# Mtx12BR_v1_1.net
KiCad netlist of a schematic drawn in EAGLE
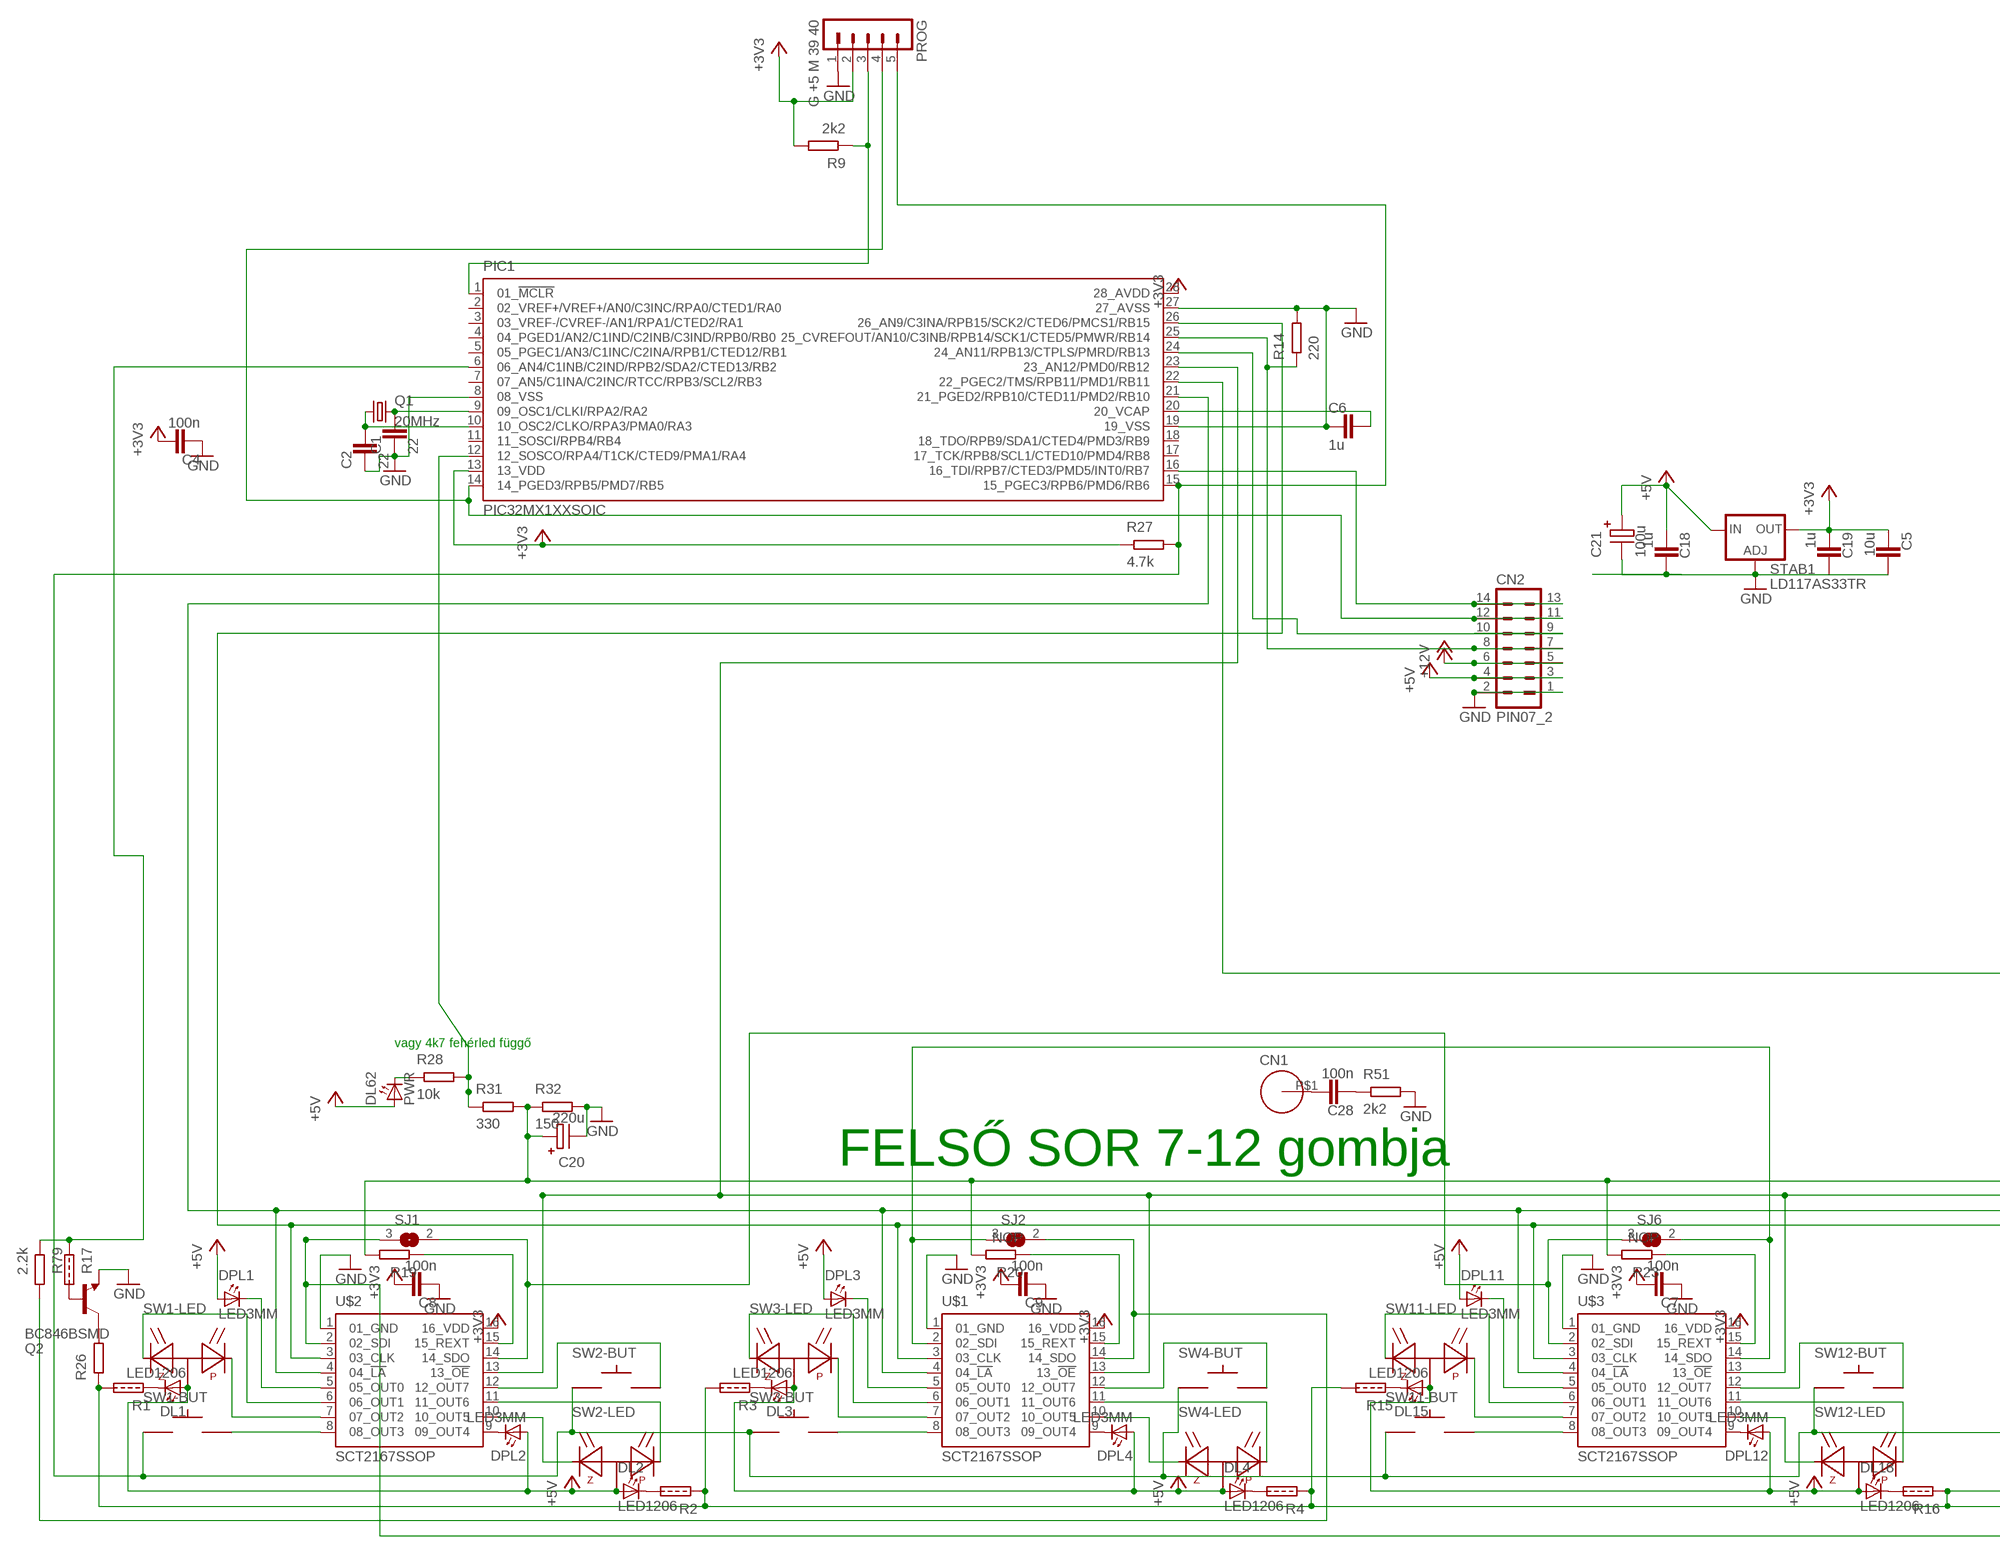
[diagram p0: schematic, sheet 1, part 1 of 2]
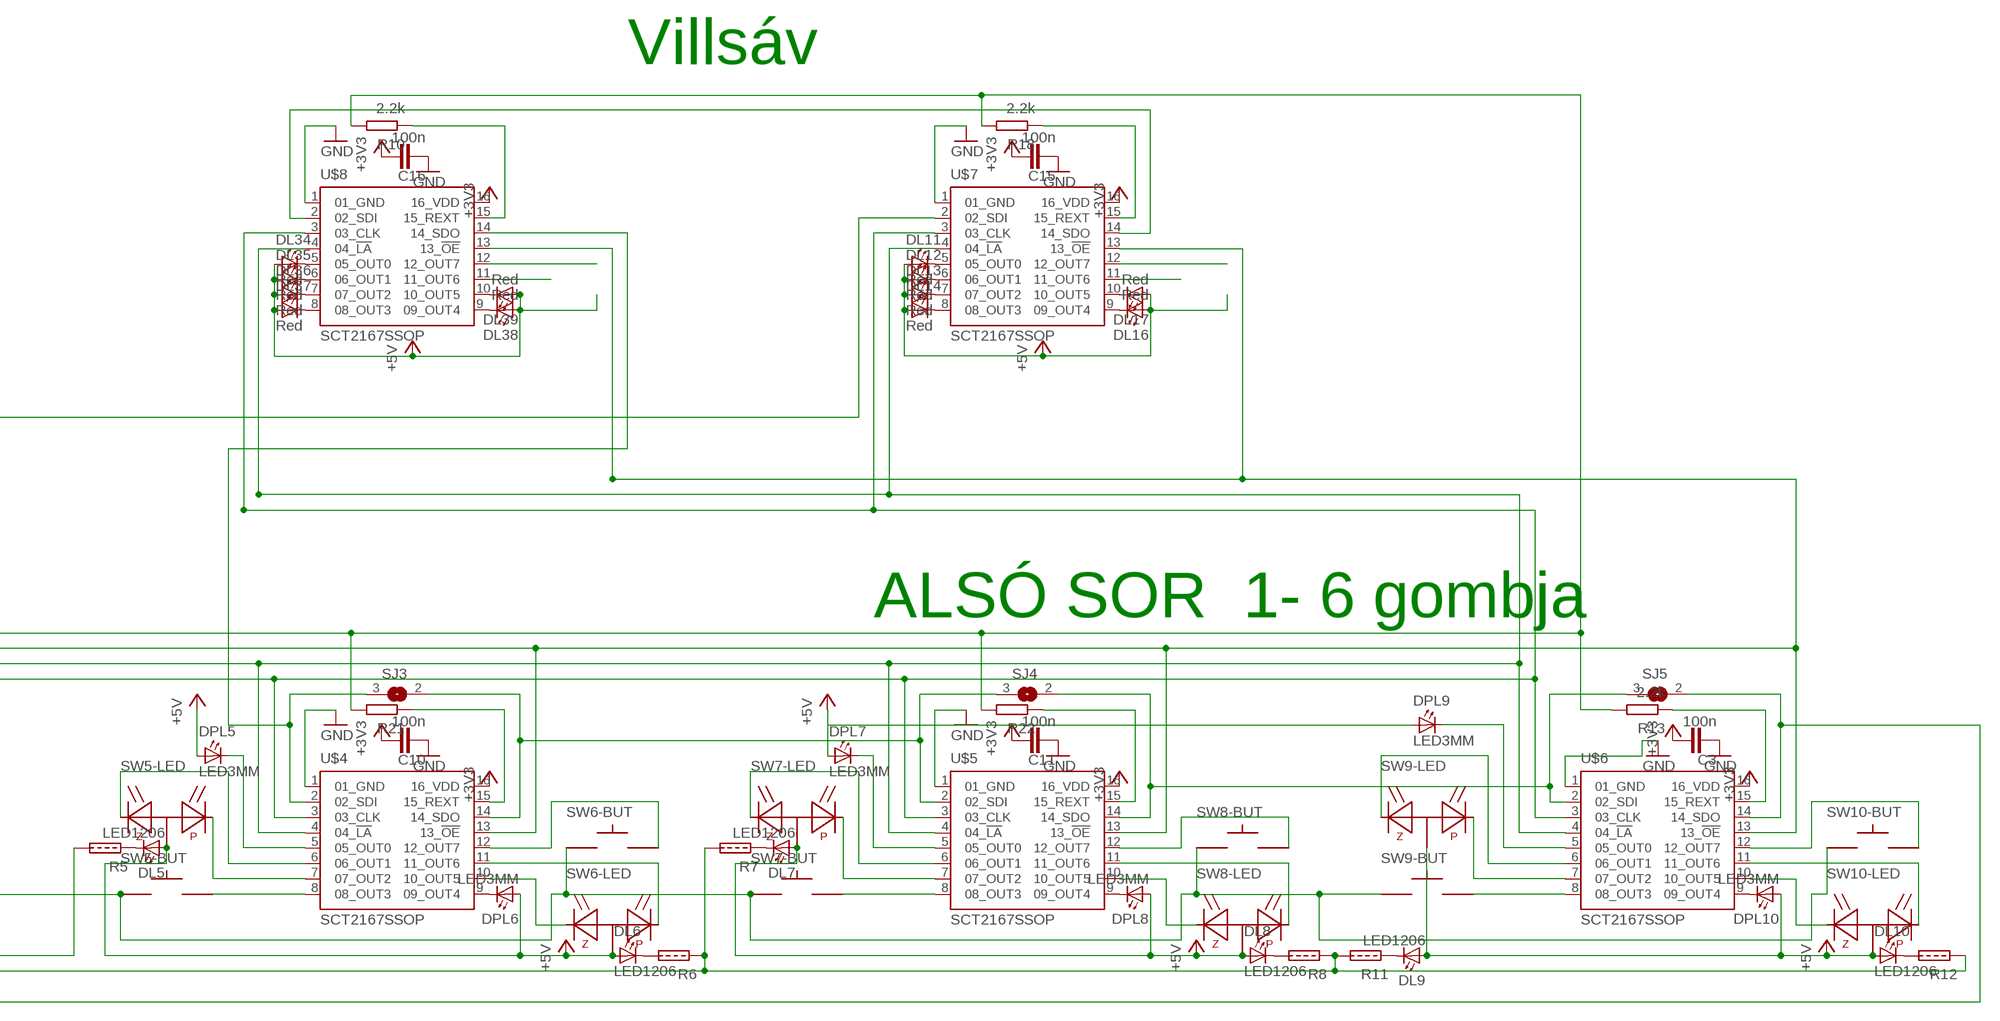
[diagram p1: schematic, sheet 1, part 2 of 2]

(export (version "E")
  (design (tool "Eeschema 10.0.6"))
  (components
    (comp (ref "C1")
      (value "22")
      (footprint "eagle-import:R0805")
      (libsource (lib "eagle-import") (part "C0805"))
    )
    (comp (ref "C2")
      (value "22")
      (footprint "eagle-import:R0805")
      (libsource (lib "eagle-import") (part "C0805"))
    )
    (comp (ref "C3")
      (value "100n")
      (footprint "eagle-import:R0805")
      (libsource (lib "eagle-import") (part "C0805"))
    )
    (comp (ref "C4")
      (value "100n")
      (footprint "eagle-import:R0805")
      (libsource (lib "eagle-import") (part "C0805"))
    )
    (comp (ref "C5")
      (value "10u")
      (footprint "eagle-import:R0805")
      (libsource (lib "eagle-import") (part "C0805"))
    )
    (comp (ref "C6")
      (value "1u")
      (footprint "eagle-import:R0805")
      (libsource (lib "eagle-import") (part "C0805"))
    )
    (comp (ref "C7")
      (value "100n")
      (footprint "eagle-import:R0805")
      (libsource (lib "eagle-import") (part "C0805"))
    )
    (comp (ref "C8")
      (value "100n")
      (footprint "eagle-import:R0805")
      (libsource (lib "eagle-import") (part "C0805"))
    )
    (comp (ref "C9")
      (value "100n")
      (footprint "eagle-import:R0805")
      (libsource (lib "eagle-import") (part "C0805"))
    )
    (comp (ref "C10")
      (value "100n")
      (footprint "eagle-import:R0805")
      (libsource (lib "eagle-import") (part "C0805"))
    )
    (comp (ref "C11")
      (value "100n")
      (footprint "eagle-import:R0805")
      (libsource (lib "eagle-import") (part "C0805"))
    )
    (comp (ref "C15")
      (value "100n")
      (footprint "eagle-import:R0805")
      (libsource (lib "eagle-import") (part "C0805"))
    )
    (comp (ref "C16")
      (value "100n")
      (footprint "eagle-import:R0805")
      (libsource (lib "eagle-import") (part "C0805"))
    )
    (comp (ref "C18")
      (value "1u")
      (footprint "eagle-import:R0805")
      (libsource (lib "eagle-import") (part "C0805"))
    )
    (comp (ref "C19")
      (value "1u")
      (footprint "eagle-import:R0805")
      (libsource (lib "eagle-import") (part "C0805"))
    )
    (comp (ref "C20")
      (value "220u")
      (footprint "eagle-import:C_EL1RASZT07")
      (libsource (lib "eagle-import") (part "C_EL1R07"))
    )
    (comp (ref "C21")
      (value "100u")
      (footprint "eagle-import:C_EL1RASZT07")
      (libsource (lib "eagle-import") (part "C_EL1R07"))
    )
    (comp (ref "C28")
      (value "100n")
      (footprint "eagle-import:R0805")
      (libsource (lib "eagle-import") (part "C0805"))
    )
    (comp (ref "CN1")
      (value "TESTCSAVAR3.5")
      (footprint "eagle-import:TESTCSAVAR_3.5")
      (libsource (lib "eagle-import") (part "TESTCSAVAR3.5"))
    )
    (comp (ref "CN2")
      (value "PIN07_2")
      (footprint "eagle-import:PIN07_2")
      (libsource (lib "eagle-import") (part "PIN07_2"))
    )
    (comp (ref "DL1")
      (value "LED1206")
      (footprint "eagle-import:R1206")
      (libsource (lib "eagle-import") (part "LED1206"))
    )
    (comp (ref "DL2")
      (value "LED1206")
      (footprint "eagle-import:R1206")
      (libsource (lib "eagle-import") (part "LED1206"))
    )
    (comp (ref "DL3")
      (value "LED1206")
      (footprint "eagle-import:R1206")
      (libsource (lib "eagle-import") (part "LED1206"))
    )
    (comp (ref "DL4")
      (value "LED1206")
      (footprint "eagle-import:R1206")
      (libsource (lib "eagle-import") (part "LED1206"))
    )
    (comp (ref "DL5")
      (value "LED1206")
      (footprint "eagle-import:R1206")
      (libsource (lib "eagle-import") (part "LED1206"))
    )
    (comp (ref "DL6")
      (value "LED1206")
      (footprint "eagle-import:R1206")
      (libsource (lib "eagle-import") (part "LED1206"))
    )
    (comp (ref "DL7")
      (value "LED1206")
      (footprint "eagle-import:R1206")
      (libsource (lib "eagle-import") (part "LED1206"))
    )
    (comp (ref "DL8")
      (value "LED1206")
      (footprint "eagle-import:R1206")
      (libsource (lib "eagle-import") (part "LED1206"))
    )
    (comp (ref "DL9")
      (value "LED1206")
      (footprint "eagle-import:R1206")
      (libsource (lib "eagle-import") (part "LED1206"))
    )
    (comp (ref "DL10")
      (value "LED1206")
      (footprint "eagle-import:R1206")
      (libsource (lib "eagle-import") (part "LED1206"))
    )
    (comp (ref "DL11")
      (value "Red")
      (footprint "eagle-import:LED5MM")
      (libsource (lib "eagle-import") (part "LED5MM"))
    )
    (comp (ref "DL12")
      (value "Red")
      (footprint "eagle-import:LED5MM")
      (libsource (lib "eagle-import") (part "LED5MM"))
    )
    (comp (ref "DL13")
      (value "Red")
      (footprint "eagle-import:LED5MM")
      (libsource (lib "eagle-import") (part "LED5MM"))
    )
    (comp (ref "DL14")
      (value "Red")
      (footprint "eagle-import:LED5MM")
      (libsource (lib "eagle-import") (part "LED5MM"))
    )
    (comp (ref "DL15")
      (value "LED1206")
      (footprint "eagle-import:R1206")
      (libsource (lib "eagle-import") (part "LED1206"))
    )
    (comp (ref "DL16")
      (value "Red")
      (footprint "eagle-import:LED5MM")
      (libsource (lib "eagle-import") (part "LED5MM"))
    )
    (comp (ref "DL17")
      (value "Red")
      (footprint "eagle-import:LED5MM")
      (libsource (lib "eagle-import") (part "LED5MM"))
    )
    (comp (ref "DL18")
      (value "LED1206")
      (footprint "eagle-import:R1206")
      (libsource (lib "eagle-import") (part "LED1206"))
    )
    (comp (ref "DL34")
      (value "Red")
      (footprint "eagle-import:LED5MM")
      (libsource (lib "eagle-import") (part "LED5MM"))
    )
    (comp (ref "DL35")
      (value "Red")
      (footprint "eagle-import:LED5MM")
      (libsource (lib "eagle-import") (part "LED5MM"))
    )
    (comp (ref "DL36")
      (value "Red")
      (footprint "eagle-import:LED5MM")
      (libsource (lib "eagle-import") (part "LED5MM"))
    )
    (comp (ref "DL37")
      (value "Red")
      (footprint "eagle-import:LED5MM")
      (libsource (lib "eagle-import") (part "LED5MM"))
    )
    (comp (ref "DL38")
      (value "Red")
      (footprint "eagle-import:LED5MM")
      (libsource (lib "eagle-import") (part "LED5MM"))
    )
    (comp (ref "DL39")
      (value "Red")
      (footprint "eagle-import:LED5MM")
      (libsource (lib "eagle-import") (part "LED5MM"))
    )
    (comp (ref "DL62")
      (value "PWR")
      (footprint "eagle-import:LED5MM")
      (libsource (lib "eagle-import") (part "LED5MM"))
    )
    (comp (ref "DPL1")
      (value "LED3MM")
      (footprint "eagle-import:LED3MM")
      (libsource (lib "eagle-import") (part "LED3MM"))
    )
    (comp (ref "DPL2")
      (value "LED3MM")
      (footprint "eagle-import:LED3MM")
      (libsource (lib "eagle-import") (part "LED3MM"))
    )
    (comp (ref "DPL3")
      (value "LED3MM")
      (footprint "eagle-import:LED3MM")
      (libsource (lib "eagle-import") (part "LED3MM"))
    )
    (comp (ref "DPL4")
      (value "LED3MM")
      (footprint "eagle-import:LED3MM")
      (libsource (lib "eagle-import") (part "LED3MM"))
    )
    (comp (ref "DPL5")
      (value "LED3MM")
      (footprint "eagle-import:LED3MM")
      (libsource (lib "eagle-import") (part "LED3MM"))
    )
    (comp (ref "DPL6")
      (value "LED3MM")
      (footprint "eagle-import:LED3MM")
      (libsource (lib "eagle-import") (part "LED3MM"))
    )
    (comp (ref "DPL7")
      (value "LED3MM")
      (footprint "eagle-import:LED3MM")
      (libsource (lib "eagle-import") (part "LED3MM"))
    )
    (comp (ref "DPL8")
      (value "LED3MM")
      (footprint "eagle-import:LED3MM")
      (libsource (lib "eagle-import") (part "LED3MM"))
    )
    (comp (ref "DPL9")
      (value "LED3MM")
      (footprint "eagle-import:LED3MM")
      (libsource (lib "eagle-import") (part "LED3MM"))
    )
    (comp (ref "DPL10")
      (value "LED3MM")
      (footprint "eagle-import:LED3MM")
      (libsource (lib "eagle-import") (part "LED3MM"))
    )
    (comp (ref "DPL11")
      (value "LED3MM")
      (footprint "eagle-import:LED3MM")
      (libsource (lib "eagle-import") (part "LED3MM"))
    )
    (comp (ref "DPL12")
      (value "LED3MM")
      (footprint "eagle-import:LED3MM")
      (libsource (lib "eagle-import") (part "LED3MM"))
    )
    (comp (ref "PIC1")
      (value "PIC32MX1XXSOIC")
      (footprint "eagle-import:SOIC127P1032X265-28N")
      (libsource (lib "eagle-import") (part "PIC32MX1XXSOIC"))
    )
    (comp (ref "PROG")
      (value "G +5 M 39 40")
      (footprint "eagle-import:PIN05_1")
      (libsource (lib "eagle-import") (part "PIN05_1"))
    )
    (comp (ref "Q1")
      (value "20MHz")
      (footprint "eagle-import:XTAL_NAGYSMD")
      (libsource (lib "eagle-import") (part "XTAL_2NAGYSMD"))
    )
    (comp (ref "Q2")
      (value "BC846BSMD")
      (footprint "eagle-import:SOT23")
      (libsource (lib "eagle-import") (part "BC846SMDB"))
    )
    (comp (ref "R1")
      (value "RNULL_EU0805")
      (footprint "eagle-import:R0805_C")
      (libsource (lib "eagle-import") (part "RNULL_EU0805"))
    )
    (comp (ref "R2")
      (value "RNULL_EU0805")
      (footprint "eagle-import:R0805_C")
      (libsource (lib "eagle-import") (part "RNULL_EU0805"))
    )
    (comp (ref "R3")
      (value "RNULL_EU0805")
      (footprint "eagle-import:R0805_C")
      (libsource (lib "eagle-import") (part "RNULL_EU0805"))
    )
    (comp (ref "R4")
      (value "RNULL_EU0805")
      (footprint "eagle-import:R0805_C")
      (libsource (lib "eagle-import") (part "RNULL_EU0805"))
    )
    (comp (ref "R5")
      (value "RNULL_EU0805")
      (footprint "eagle-import:R0805_C")
      (libsource (lib "eagle-import") (part "RNULL_EU0805"))
    )
    (comp (ref "R6")
      (value "RNULL_EU0805")
      (footprint "eagle-import:R0805_C")
      (libsource (lib "eagle-import") (part "RNULL_EU0805"))
    )
    (comp (ref "R7")
      (value "RNULL_EU0805")
      (footprint "eagle-import:R0805_C")
      (libsource (lib "eagle-import") (part "RNULL_EU0805"))
    )
    (comp (ref "R8")
      (value "RNULL_EU0805")
      (footprint "eagle-import:R0805_C")
      (libsource (lib "eagle-import") (part "RNULL_EU0805"))
    )
    (comp (ref "R9")
      (value "2k2")
      (footprint "eagle-import:R0805")
      (libsource (lib "eagle-import") (part "R_EU0805"))
    )
    (comp (ref "R10")
      (value "2.2k")
      (footprint "eagle-import:R0805")
      (libsource (lib "eagle-import") (part "R_EU0805"))
    )
    (comp (ref "R11")
      (value "RNULL_EU0805")
      (footprint "eagle-import:R0805_C")
      (libsource (lib "eagle-import") (part "RNULL_EU0805"))
    )
    (comp (ref "R12")
      (value "RNULL_EU0805")
      (footprint "eagle-import:R0805_C")
      (libsource (lib "eagle-import") (part "RNULL_EU0805"))
    )
    (comp (ref "R13")
      (value "2.2k")
      (footprint "eagle-import:R0805")
      (libsource (lib "eagle-import") (part "R_EU0805"))
    )
    (comp (ref "R14")
      (value "220")
      (footprint "eagle-import:R0805")
      (libsource (lib "eagle-import") (part "R_EU0805"))
    )
    (comp (ref "R15")
      (value "RNULL_EU0805")
      (footprint "eagle-import:R0805_C")
      (libsource (lib "eagle-import") (part "RNULL_EU0805"))
    )
    (comp (ref "R16")
      (value "RNULL_EU0805")
      (footprint "eagle-import:R0805_C")
      (libsource (lib "eagle-import") (part "RNULL_EU0805"))
    )
    (comp (ref "R17")
      (value "RNULL_EU0805")
      (footprint "eagle-import:R0805_C")
      (libsource (lib "eagle-import") (part "RNULL_EU0805"))
    )
    (comp (ref "R18")
      (value "2.2k")
      (footprint "eagle-import:R0805")
      (libsource (lib "eagle-import") (part "R_EU0805"))
    )
    (comp (ref "R19")
      (value "R_EU0805")
      (footprint "eagle-import:R0805")
      (libsource (lib "eagle-import") (part "R_EU0805"))
    )
    (comp (ref "R20")
      (value "NOP")
      (footprint "eagle-import:R0805")
      (libsource (lib "eagle-import") (part "R_EU0805"))
    )
    (comp (ref "R21")
      (value "R_EU0805")
      (footprint "eagle-import:R0805")
      (libsource (lib "eagle-import") (part "R_EU0805"))
    )
    (comp (ref "R22")
      (value "R_EU0805")
      (footprint "eagle-import:R0805")
      (libsource (lib "eagle-import") (part "R_EU0805"))
    )
    (comp (ref "R23")
      (value "NOP")
      (footprint "eagle-import:R0805")
      (libsource (lib "eagle-import") (part "R_EU0805"))
    )
    (comp (ref "R26")
      (value "R_EU0805")
      (footprint "eagle-import:R0805")
      (libsource (lib "eagle-import") (part "R_EU0805"))
    )
    (comp (ref "R27")
      (value "4.7k")
      (footprint "eagle-import:R0805")
      (libsource (lib "eagle-import") (part "R_EU0805"))
    )
    (comp (ref "R28")
      (value "10k")
      (footprint "eagle-import:R0805")
      (libsource (lib "eagle-import") (part "R_EU0805"))
    )
    (comp (ref "R31")
      (value "330")
      (footprint "eagle-import:R0805")
      (libsource (lib "eagle-import") (part "R_EU0805"))
    )
    (comp (ref "R32")
      (value "150")
      (footprint "eagle-import:R0805")
      (libsource (lib "eagle-import") (part "R_EU0805"))
    )
    (comp (ref "R51")
      (value "2k2")
      (footprint "eagle-import:R0805")
      (libsource (lib "eagle-import") (part "R_EU0805"))
    )
    (comp (ref "R79")
      (value "2.2k")
      (footprint "eagle-import:R0805")
      (libsource (lib "eagle-import") (part "R_EU0805"))
    )
    (comp (ref "SJ1") (value "SJ") (footprint "eagle-import:SJ") (libsource (lib "eagle-import") (part "SJ")))
    (comp (ref "SJ2") (value "SJ") (footprint "eagle-import:SJ") (libsource (lib "eagle-import") (part "SJ")))
    (comp (ref "SJ3") (value "SJ") (footprint "eagle-import:SJ") (libsource (lib "eagle-import") (part "SJ")))
    (comp (ref "SJ4") (value "SJ") (footprint "eagle-import:SJ") (libsource (lib "eagle-import") (part "SJ")))
    (comp (ref "SJ5") (value "SJ") (footprint "eagle-import:SJ") (libsource (lib "eagle-import") (part "SJ")))
    (comp (ref "SJ6") (value "SJ") (footprint "eagle-import:SJ") (libsource (lib "eagle-import") (part "SJ")))
    (comp (ref "STAB1")
      (value "LD117AS33TR")
      (footprint "eagle-import:SOT223")
      (libsource (lib "eagle-import") (part "LD117A?S33TR"))
    )
    (comp (ref "SW1")
      (value "SPG2")
      (footprint "eagle-import:SPG2_3LED")
      (libsource (lib "eagle-import") (part "SPG2"))
    )
    (comp (ref "SW2")
      (value "SPG2")
      (footprint "eagle-import:SPG2_3LED")
      (libsource (lib "eagle-import") (part "SPG2"))
    )
    (comp (ref "SW3")
      (value "SPG2")
      (footprint "eagle-import:SPG2_3LED")
      (libsource (lib "eagle-import") (part "SPG2"))
    )
    (comp (ref "SW4")
      (value "SPG2")
      (footprint "eagle-import:SPG2_3LED")
      (libsource (lib "eagle-import") (part "SPG2"))
    )
    (comp (ref "SW5")
      (value "SPG2")
      (footprint "eagle-import:SPG2_3LED")
      (libsource (lib "eagle-import") (part "SPG2"))
    )
    (comp (ref "SW6")
      (value "SPG2")
      (footprint "eagle-import:SPG2_3LED")
      (libsource (lib "eagle-import") (part "SPG2"))
    )
    (comp (ref "SW7")
      (value "SPG2")
      (footprint "eagle-import:SPG2_3LED")
      (libsource (lib "eagle-import") (part "SPG2"))
    )
    (comp (ref "SW8")
      (value "SPG2")
      (footprint "eagle-import:SPG2_3LED")
      (libsource (lib "eagle-import") (part "SPG2"))
    )
    (comp (ref "SW9")
      (value "SPG2")
      (footprint "eagle-import:SPG2_3LED")
      (libsource (lib "eagle-import") (part "SPG2"))
    )
    (comp (ref "SW10")
      (value "SPG2")
      (footprint "eagle-import:SPG2_3LED")
      (libsource (lib "eagle-import") (part "SPG2"))
    )
    (comp (ref "SW11")
      (value "SPG2")
      (footprint "eagle-import:SPG2_3LED")
      (libsource (lib "eagle-import") (part "SPG2"))
    )
    (comp (ref "SW12")
      (value "SPG2")
      (footprint "eagle-import:SPG2_3LED")
      (libsource (lib "eagle-import") (part "SPG2"))
    )
    (comp (ref "U$1")
      (value "SCT2167SSOP")
      (footprint "eagle-import:SSOP")
      (libsource (lib "eagle-import") (part "SCT2167SSOP"))
    )
    (comp (ref "U$2")
      (value "SCT2167SSOP")
      (footprint "eagle-import:SSOP")
      (libsource (lib "eagle-import") (part "SCT2167SSOP"))
    )
    (comp (ref "U$3")
      (value "SCT2167SSOP")
      (footprint "eagle-import:SSOP")
      (libsource (lib "eagle-import") (part "SCT2167SSOP"))
    )
    (comp (ref "U$4")
      (value "SCT2167SSOP")
      (footprint "eagle-import:SSOP")
      (libsource (lib "eagle-import") (part "SCT2167SSOP"))
    )
    (comp (ref "U$5")
      (value "SCT2167SSOP")
      (footprint "eagle-import:SSOP")
      (libsource (lib "eagle-import") (part "SCT2167SSOP"))
    )
    (comp (ref "U$6")
      (value "SCT2167SSOP")
      (footprint "eagle-import:SSOP")
      (libsource (lib "eagle-import") (part "SCT2167SSOP"))
    )
    (comp (ref "U$7")
      (value "SCT2167SSOP")
      (footprint "eagle-import:SSOP")
      (libsource (lib "eagle-import") (part "SCT2167SSOP"))
    )
    (comp (ref "U$8")
      (value "SCT2167SSOP")
      (footprint "eagle-import:SSOP")
      (libsource (lib "eagle-import") (part "SCT2167SSOP"))
    )
  )
  (nets
    (net (code "1") (name "+3V3") (class "Default")
      (node (ref "C10") (pin "1") (pinfunction "1_1") (pintype "passive"))
      (node (ref "C11") (pin "1") (pinfunction "1_1") (pintype "passive"))
      (node (ref "C15") (pin "1") (pinfunction "1_1") (pintype "passive"))
      (node (ref "C16") (pin "1") (pinfunction "1_1") (pintype "passive"))
      (node (ref "C19") (pin "2") (pinfunction "2_2") (pintype "passive"))
      (node (ref "C3") (pin "1") (pinfunction "1_1") (pintype "passive"))
      (node (ref "C4") (pin "1") (pinfunction "1_1") (pintype "passive"))
      (node (ref "C5") (pin "2") (pinfunction "2_2") (pintype "passive"))
      (node (ref "C7") (pin "1") (pinfunction "1_1") (pintype "passive"))
      (node (ref "C8") (pin "1") (pinfunction "1_1") (pintype "passive"))
      (node (ref "C9") (pin "1") (pinfunction "1_1") (pintype "passive"))
      (node (ref "PIC1") (pin "13") (pinfunction "13_VDD_13") (pintype "bidirectional"))
      (node (ref "PIC1") (pin "28") (pinfunction "28_AVDD_28") (pintype "bidirectional"))
      (node (ref "PROG") (pin "2") (pinfunction "2_2") (pintype "passive"))
      (node (ref "R27") (pin "1") (pinfunction "A_1") (pintype "passive"))
      (node (ref "R9") (pin "2") (pinfunction "E_2") (pintype "passive"))
      (node (ref "STAB1") (pin "4") (pinfunction "OUT_4") (pintype "passive"))
      (node (ref "U$1") (pin "16") (pinfunction "16_VDD_16") (pintype "power_in"))
      (node (ref "U$2") (pin "16") (pinfunction "16_VDD_16") (pintype "power_in"))
      (node (ref "U$3") (pin "16") (pinfunction "16_VDD_16") (pintype "power_in"))
      (node (ref "U$4") (pin "16") (pinfunction "16_VDD_16") (pintype "power_in"))
      (node (ref "U$5") (pin "16") (pinfunction "16_VDD_16") (pintype "power_in"))
      (node (ref "U$6") (pin "16") (pinfunction "16_VDD_16") (pintype "power_in"))
      (node (ref "U$7") (pin "16") (pinfunction "16_VDD_16") (pintype "power_in"))
      (node (ref "U$8") (pin "16") (pinfunction "16_VDD_16") (pintype "power_in"))
    )
    (net (code "2") (name "+5V") (class "Default")
      (node (ref "C18") (pin "2") (pinfunction "2_2") (pintype "passive"))
      (node (ref "C21") (pin "P+") (pinfunction "P+_P+") (pintype "passive"))
      (node (ref "CN2") (pin "3") (pinfunction "3_3") (pintype "passive"))
      (node (ref "CN2") (pin "4") (pinfunction "4_4") (pintype "passive"))
      (node (ref "DL1") (pin "1") (pinfunction "A_1") (pintype "passive"))
      (node (ref "DL10") (pin "1") (pinfunction "A_1") (pintype "passive"))
      (node (ref "DL11") (pin "A") (pinfunction "A_A") (pintype "passive"))
      (node (ref "DL12") (pin "A") (pinfunction "A_A") (pintype "passive"))
      (node (ref "DL13") (pin "A") (pinfunction "A_A") (pintype "passive"))
      (node (ref "DL14") (pin "A") (pinfunction "A_A") (pintype "passive"))
      (node (ref "DL15") (pin "1") (pinfunction "A_1") (pintype "passive"))
      (node (ref "DL16") (pin "A") (pinfunction "A_A") (pintype "passive"))
      (node (ref "DL17") (pin "A") (pinfunction "A_A") (pintype "passive"))
      (node (ref "DL18") (pin "1") (pinfunction "A_1") (pintype "passive"))
      (node (ref "DL2") (pin "1") (pinfunction "A_1") (pintype "passive"))
      (node (ref "DL3") (pin "1") (pinfunction "A_1") (pintype "passive"))
      (node (ref "DL34") (pin "A") (pinfunction "A_A") (pintype "passive"))
      (node (ref "DL35") (pin "A") (pinfunction "A_A") (pintype "passive"))
      (node (ref "DL36") (pin "A") (pinfunction "A_A") (pintype "passive"))
      (node (ref "DL37") (pin "A") (pinfunction "A_A") (pintype "passive"))
      (node (ref "DL38") (pin "A") (pinfunction "A_A") (pintype "passive"))
      (node (ref "DL39") (pin "A") (pinfunction "A_A") (pintype "passive"))
      (node (ref "DL4") (pin "1") (pinfunction "A_1") (pintype "passive"))
      (node (ref "DL5") (pin "1") (pinfunction "A_1") (pintype "passive"))
      (node (ref "DL6") (pin "1") (pinfunction "A_1") (pintype "passive"))
      (node (ref "DL62") (pin "A") (pinfunction "A_A") (pintype "passive"))
      (node (ref "DL7") (pin "1") (pinfunction "A_1") (pintype "passive"))
      (node (ref "DL8") (pin "1") (pinfunction "A_1") (pintype "passive"))
      (node (ref "DL9") (pin "1") (pinfunction "A_1") (pintype "passive"))
      (node (ref "DPL1") (pin "A") (pinfunction "A_A") (pintype "passive"))
      (node (ref "DPL10") (pin "A") (pinfunction "A_A") (pintype "passive"))
      (node (ref "DPL11") (pin "A") (pinfunction "A_A") (pintype "passive"))
      (node (ref "DPL12") (pin "A") (pinfunction "A_A") (pintype "passive"))
      (node (ref "DPL2") (pin "A") (pinfunction "A_A") (pintype "passive"))
      (node (ref "DPL3") (pin "A") (pinfunction "A_A") (pintype "passive"))
      (node (ref "DPL4") (pin "A") (pinfunction "A_A") (pintype "passive"))
      (node (ref "DPL5") (pin "A") (pinfunction "A_A") (pintype "passive"))
      (node (ref "DPL6") (pin "A") (pinfunction "A_A") (pintype "passive"))
      (node (ref "DPL7") (pin "A") (pinfunction "A_A") (pintype "passive"))
      (node (ref "DPL8") (pin "A") (pinfunction "A_A") (pintype "passive"))
      (node (ref "DPL9") (pin "A") (pinfunction "A_A") (pintype "passive"))
      (node (ref "STAB1") (pin "3") (pinfunction "IN_3") (pintype "input"))
      (node (ref "SW1") (pin "LED+") (pinfunction "+_LED+") (pintype "bidirectional"))
      (node (ref "SW10") (pin "LED+") (pinfunction "+_LED+") (pintype "bidirectional"))
      (node (ref "SW11") (pin "LED+") (pinfunction "+_LED+") (pintype "bidirectional"))
      (node (ref "SW12") (pin "LED+") (pinfunction "+_LED+") (pintype "bidirectional"))
      (node (ref "SW2") (pin "LED+") (pinfunction "+_LED+") (pintype "bidirectional"))
      (node (ref "SW3") (pin "LED+") (pinfunction "+_LED+") (pintype "bidirectional"))
      (node (ref "SW4") (pin "LED+") (pinfunction "+_LED+") (pintype "bidirectional"))
      (node (ref "SW5") (pin "LED+") (pinfunction "+_LED+") (pintype "bidirectional"))
      (node (ref "SW6") (pin "LED+") (pinfunction "+_LED+") (pintype "bidirectional"))
      (node (ref "SW7") (pin "LED+") (pinfunction "+_LED+") (pintype "bidirectional"))
      (node (ref "SW8") (pin "LED+") (pinfunction "+_LED+") (pintype "bidirectional"))
      (node (ref "SW9") (pin "LED+") (pinfunction "+_LED+") (pintype "bidirectional"))
    )
    (net (code "3") (name "+12V") (class "Default")
      (node (ref "CN2") (pin "5") (pinfunction "5_5") (pintype "passive"))
      (node (ref "CN2") (pin "6") (pinfunction "6_6") (pintype "passive"))
    )
    (net (code "4") (name "GND") (class "Default")
      (node (ref "C1") (pin "2") (pinfunction "2_2") (pintype "passive"))
      (node (ref "C10") (pin "2") (pinfunction "2_2") (pintype "passive"))
      (node (ref "C11") (pin "2") (pinfunction "2_2") (pintype "passive"))
      (node (ref "C15") (pin "2") (pinfunction "2_2") (pintype "passive"))
      (node (ref "C16") (pin "2") (pinfunction "2_2") (pintype "passive"))
      (node (ref "C18") (pin "1") (pinfunction "1_1") (pintype "passive"))
      (node (ref "C19") (pin "1") (pinfunction "1_1") (pintype "passive"))
      (node (ref "C2") (pin "2") (pinfunction "2_2") (pintype "passive"))
      (node (ref "C20") (pin "P-") (pinfunction "P-_P-") (pintype "passive"))
      (node (ref "C21") (pin "P-") (pinfunction "P-_P-") (pintype "passive"))
      (node (ref "C3") (pin "2") (pinfunction "2_2") (pintype "passive"))
      (node (ref "C4") (pin "2") (pinfunction "2_2") (pintype "passive"))
      (node (ref "C5") (pin "1") (pinfunction "1_1") (pintype "passive"))
      (node (ref "C6") (pin "2") (pinfunction "2_2") (pintype "passive"))
      (node (ref "C7") (pin "2") (pinfunction "2_2") (pintype "passive"))
      (node (ref "C8") (pin "2") (pinfunction "2_2") (pintype "passive"))
      (node (ref "C9") (pin "2") (pinfunction "2_2") (pintype "passive"))
      (node (ref "CN2") (pin "1") (pinfunction "1_1") (pintype "passive"))
      (node (ref "CN2") (pin "2") (pinfunction "2_2") (pintype "passive"))
      (node (ref "PIC1") (pin "19") (pinfunction "19_VSS_19") (pintype "power_in"))
      (node (ref "PIC1") (pin "27") (pinfunction "27_AVSS_27") (pintype "bidirectional"))
      (node (ref "PIC1") (pin "8") (pinfunction "08_VSS_8") (pintype "power_in"))
      (node (ref "PROG") (pin "1") (pinfunction "1_1") (pintype "passive"))
      (node (ref "Q2") (pin "2") (pinfunction "E_2") (pintype "passive"))
      (node (ref "R14") (pin "2") (pinfunction "E_2") (pintype "passive"))
      (node (ref "R32") (pin "2") (pinfunction "E_2") (pintype "passive"))
      (node (ref "R51") (pin "2") (pinfunction "E_2") (pintype "passive"))
      (node (ref "STAB1") (pin "1") (pinfunction "ADJ_1") (pintype "input"))
      (node (ref "U$1") (pin "1") (pinfunction "01_GND_1") (pintype "power_in"))
      (node (ref "U$2") (pin "1") (pinfunction "01_GND_1") (pintype "power_in"))
      (node (ref "U$3") (pin "1") (pinfunction "01_GND_1") (pintype "power_in"))
      (node (ref "U$4") (pin "1") (pinfunction "01_GND_1") (pintype "power_in"))
      (node (ref "U$5") (pin "1") (pinfunction "01_GND_1") (pintype "power_in"))
      (node (ref "U$6") (pin "1") (pinfunction "01_GND_1") (pintype "power_in"))
      (node (ref "U$7") (pin "1") (pinfunction "01_GND_1") (pintype "power_in"))
      (node (ref "U$8") (pin "1") (pinfunction "01_GND_1") (pintype "power_in"))
    )
    (net (code "5") (name "Net-(CN1-1)") (class "Default")
      (node (ref "C28") (pin "1") (pinfunction "1_1") (pintype "passive"))
      (node (ref "CN1") (pin "P$1") (pinfunction "1_P$1") (pintype "passive"))
    )
    (net (code "6") (name "Net-(DL1-C)") (class "Default")
      (node (ref "DL1") (pin "2") (pinfunction "C_2") (pintype "passive"))
      (node (ref "R1") (pin "1") (pinfunction "A_1") (pintype "passive"))
    )
    (net (code "7") (name "Net-(DL2-C)") (class "Default")
      (node (ref "DL2") (pin "2") (pinfunction "C_2") (pintype "passive"))
      (node (ref "R2") (pin "2") (pinfunction "E_2") (pintype "passive"))
    )
    (net (code "8") (name "Net-(DL3-C)") (class "Default")
      (node (ref "DL3") (pin "2") (pinfunction "C_2") (pintype "passive"))
      (node (ref "R3") (pin "1") (pinfunction "A_1") (pintype "passive"))
    )
    (net (code "9") (name "Net-(DL4-C)") (class "Default")
      (node (ref "DL4") (pin "2") (pinfunction "C_2") (pintype "passive"))
      (node (ref "R4") (pin "2") (pinfunction "E_2") (pintype "passive"))
    )
    (net (code "10") (name "Net-(DL5-C)") (class "Default")
      (node (ref "DL5") (pin "2") (pinfunction "C_2") (pintype "passive"))
      (node (ref "R5") (pin "1") (pinfunction "A_1") (pintype "passive"))
    )
    (net (code "11") (name "Net-(DL6-C)") (class "Default")
      (node (ref "DL6") (pin "2") (pinfunction "C_2") (pintype "passive"))
      (node (ref "R6") (pin "2") (pinfunction "E_2") (pintype "passive"))
    )
    (net (code "12") (name "Net-(DL7-C)") (class "Default")
      (node (ref "DL7") (pin "2") (pinfunction "C_2") (pintype "passive"))
      (node (ref "R7") (pin "1") (pinfunction "A_1") (pintype "passive"))
    )
    (net (code "13") (name "Net-(DL8-C)") (class "Default")
      (node (ref "DL8") (pin "2") (pinfunction "C_2") (pintype "passive"))
      (node (ref "R8") (pin "2") (pinfunction "E_2") (pintype "passive"))
    )
    (net (code "14") (name "Net-(DL9-C)") (class "Default")
      (node (ref "DL9") (pin "2") (pinfunction "C_2") (pintype "passive"))
      (node (ref "R11") (pin "1") (pinfunction "A_1") (pintype "passive"))
    )
    (net (code "15") (name "Net-(DL10-C)") (class "Default")
      (node (ref "DL10") (pin "2") (pinfunction "C_2") (pintype "passive"))
      (node (ref "R12") (pin "2") (pinfunction "E_2") (pintype "passive"))
    )
    (net (code "16") (name "Net-(DL11-C)") (class "Default")
      (node (ref "DL11") (pin "K") (pinfunction "C_K") (pintype "passive"))
      (node (ref "U$7") (pin "5") (pinfunction "05_OUT0_5") (pintype "output"))
    )
    (net (code "17") (name "Net-(DL12-C)") (class "Default")
      (node (ref "DL12") (pin "K") (pinfunction "C_K") (pintype "passive"))
      (node (ref "U$7") (pin "6") (pinfunction "06_OUT1_6") (pintype "output"))
    )
    (net (code "18") (name "Net-(DL13-C)") (class "Default")
      (node (ref "DL13") (pin "K") (pinfunction "C_K") (pintype "passive"))
      (node (ref "U$7") (pin "7") (pinfunction "07_OUT2_7") (pintype "output"))
    )
    (net (code "19") (name "Net-(DL14-C)") (class "Default")
      (node (ref "DL14") (pin "K") (pinfunction "C_K") (pintype "passive"))
      (node (ref "U$7") (pin "8") (pinfunction "08_OUT3_8") (pintype "output"))
    )
    (net (code "20") (name "Net-(DL15-C)") (class "Default")
      (node (ref "DL15") (pin "2") (pinfunction "C_2") (pintype "passive"))
      (node (ref "R15") (pin "1") (pinfunction "A_1") (pintype "passive"))
    )
    (net (code "21") (name "Net-(DL16-C)") (class "Default")
      (node (ref "DL16") (pin "K") (pinfunction "C_K") (pintype "passive"))
      (node (ref "U$7") (pin "9") (pinfunction "09_OUT4_9") (pintype "output"))
    )
    (net (code "22") (name "Net-(DL17-C)") (class "Default")
      (node (ref "DL17") (pin "K") (pinfunction "C_K") (pintype "passive"))
      (node (ref "U$7") (pin "10") (pinfunction "10_OUT5_10") (pintype "output"))
    )
    (net (code "23") (name "Net-(DL18-C)") (class "Default")
      (node (ref "DL18") (pin "2") (pinfunction "C_2") (pintype "passive"))
      (node (ref "R16") (pin "2") (pinfunction "E_2") (pintype "passive"))
    )
    (net (code "24") (name "Net-(DL34-C)") (class "Default")
      (node (ref "DL34") (pin "K") (pinfunction "C_K") (pintype "passive"))
      (node (ref "U$8") (pin "5") (pinfunction "05_OUT0_5") (pintype "output"))
    )
    (net (code "25") (name "Net-(DL35-C)") (class "Default")
      (node (ref "DL35") (pin "K") (pinfunction "C_K") (pintype "passive"))
      (node (ref "U$8") (pin "6") (pinfunction "06_OUT1_6") (pintype "output"))
    )
    (net (code "26") (name "Net-(DL36-C)") (class "Default")
      (node (ref "DL36") (pin "K") (pinfunction "C_K") (pintype "passive"))
      (node (ref "U$8") (pin "7") (pinfunction "07_OUT2_7") (pintype "output"))
    )
    (net (code "27") (name "Net-(DL37-C)") (class "Default")
      (node (ref "DL37") (pin "K") (pinfunction "C_K") (pintype "passive"))
      (node (ref "U$8") (pin "8") (pinfunction "08_OUT3_8") (pintype "output"))
    )
    (net (code "28") (name "Net-(DL38-C)") (class "Default")
      (node (ref "DL38") (pin "K") (pinfunction "C_K") (pintype "passive"))
      (node (ref "U$8") (pin "9") (pinfunction "09_OUT4_9") (pintype "output"))
    )
    (net (code "29") (name "Net-(DL39-C)") (class "Default")
      (node (ref "DL39") (pin "K") (pinfunction "C_K") (pintype "passive"))
      (node (ref "U$8") (pin "10") (pinfunction "10_OUT5_10") (pintype "output"))
    )
    (net (code "30") (name "Net-(DL62-C)") (class "Default")
      (node (ref "DL62") (pin "K") (pinfunction "C_K") (pintype "passive"))
      (node (ref "R28") (pin "1") (pinfunction "A_1") (pintype "passive"))
    )
    (net (code "31") (name "Net-(DPL1-C)") (class "Default")
      (node (ref "DPL1") (pin "K") (pinfunction "C_K") (pintype "passive"))
      (node (ref "U$2") (pin "5") (pinfunction "05_OUT0_5") (pintype "output"))
    )
    (net (code "32") (name "Net-(DPL2-C)") (class "Default")
      (node (ref "DPL2") (pin "K") (pinfunction "C_K") (pintype "passive"))
      (node (ref "U$2") (pin "9") (pinfunction "09_OUT4_9") (pintype "output"))
    )
    (net (code "33") (name "Net-(DPL3-C)") (class "Default")
      (node (ref "DPL3") (pin "K") (pinfunction "C_K") (pintype "passive"))
      (node (ref "U$1") (pin "5") (pinfunction "05_OUT0_5") (pintype "output"))
    )
    (net (code "34") (name "Net-(DPL4-C)") (class "Default")
      (node (ref "DPL4") (pin "K") (pinfunction "C_K") (pintype "passive"))
      (node (ref "U$1") (pin "9") (pinfunction "09_OUT4_9") (pintype "output"))
    )
    (net (code "35") (name "Net-(DPL5-C)") (class "Default")
      (node (ref "DPL5") (pin "K") (pinfunction "C_K") (pintype "passive"))
      (node (ref "U$4") (pin "5") (pinfunction "05_OUT0_5") (pintype "output"))
    )
    (net (code "36") (name "Net-(DPL6-C)") (class "Default")
      (node (ref "DPL6") (pin "K") (pinfunction "C_K") (pintype "passive"))
      (node (ref "U$4") (pin "9") (pinfunction "09_OUT4_9") (pintype "output"))
    )
    (net (code "37") (name "Net-(DPL7-C)") (class "Default")
      (node (ref "DPL7") (pin "K") (pinfunction "C_K") (pintype "passive"))
      (node (ref "U$5") (pin "5") (pinfunction "05_OUT0_5") (pintype "output"))
    )
    (net (code "38") (name "Net-(DPL8-C)") (class "Default")
      (node (ref "DPL8") (pin "K") (pinfunction "C_K") (pintype "passive"))
      (node (ref "U$5") (pin "9") (pinfunction "09_OUT4_9") (pintype "output"))
    )
    (net (code "39") (name "Net-(DPL9-C)") (class "Default")
      (node (ref "DPL9") (pin "K") (pinfunction "C_K") (pintype "passive"))
      (node (ref "U$6") (pin "5") (pinfunction "05_OUT0_5") (pintype "output"))
    )
    (net (code "40") (name "Net-(DPL10-C)") (class "Default")
      (node (ref "DPL10") (pin "K") (pinfunction "C_K") (pintype "passive"))
      (node (ref "U$6") (pin "9") (pinfunction "09_OUT4_9") (pintype "output"))
    )
    (net (code "41") (name "Net-(DPL11-C)") (class "Default")
      (node (ref "DPL11") (pin "K") (pinfunction "C_K") (pintype "passive"))
      (node (ref "U$3") (pin "5") (pinfunction "05_OUT0_5") (pintype "output"))
    )
    (net (code "42") (name "Net-(DPL12-C)") (class "Default")
      (node (ref "DPL12") (pin "K") (pinfunction "C_K") (pintype "passive"))
      (node (ref "U$3") (pin "9") (pinfunction "09_OUT4_9") (pintype "output"))
    )
    (net (code "43") (name "Net-(PIC1-01_~{MCLR})") (class "Default")
      (node (ref "PIC1") (pin "1") (pinfunction "01_~{MCLR}_1") (pintype "input"))
      (node (ref "PROG") (pin "3") (pinfunction "3_3") (pintype "passive"))
      (node (ref "R9") (pin "1") (pinfunction "A_1") (pintype "passive"))
    )
    (net (code "44") (name "Net-(PIC1-06_AN4{slash}C1INB{slash}C2IND{slash}RPB2{slash}SDA2{slash}CTED13{slash}RB2)") (class "Default")
      (node (ref "PIC1") (pin "6") (pinfunction "06_AN4/C1INB/C2IND/RPB2/SDA2/CTED13/RB2_6") (pintype "bidirectional"))
      (node (ref "R17") (pin "1") (pinfunction "A_1") (pintype "passive"))
      (node (ref "R79") (pin "1") (pinfunction "A_1") (pintype "passive"))
    )
    (net (code "45") (name "Net-(PIC1-09_OSC1{slash}CLKI{slash}RPA2{slash}RA2)") (class "Default")
      (node (ref "C1") (pin "1") (pinfunction "1_1") (pintype "passive"))
      (node (ref "PIC1") (pin "9") (pinfunction "09_OSC1/CLKI/RPA2/RA2_9") (pintype "bidirectional"))
      (node (ref "Q1") (pin "P$2") (pinfunction "2_P$2") (pintype "passive"))
    )
    (net (code "46") (name "Net-(PIC1-10_OSC2{slash}CLKO{slash}RPA3{slash}PMA0{slash}RA3)") (class "Default")
      (node (ref "C2") (pin "1") (pinfunction "1_1") (pintype "passive"))
      (node (ref "PIC1") (pin "10") (pinfunction "10_OSC2/CLKO/RPA3/PMA0/RA3_10") (pintype "bidirectional"))
      (node (ref "Q1") (pin "P$1") (pinfunction "1_P$1") (pintype "passive"))
    )
    (net (code "47") (name "Net-(PIC1-12_SOSCO{slash}RPA4{slash}T1CK{slash}CTED9{slash}PMA1{slash}RA4)") (class "Default")
      (node (ref "PIC1") (pin "12") (pinfunction "12_SOSCO/RPA4/T1CK/CTED9/PMA1/RA4_12") (pintype "bidirectional"))
      (node (ref "R28") (pin "2") (pinfunction "E_2") (pintype "passive"))
      (node (ref "R31") (pin "1") (pinfunction "A_1") (pintype "passive"))
    )
    (net (code "48") (name "Net-(PIC1-14_PGED3{slash}RPB5{slash}PMD7{slash}RB5)") (class "Default")
      (node (ref "CN2") (pin "11") (pinfunction "11_11") (pintype "passive"))
      (node (ref "CN2") (pin "12") (pinfunction "12_12") (pintype "passive"))
      (node (ref "PIC1") (pin "14") (pinfunction "14_PGED3/RPB5/PMD7/RB5_14") (pintype "bidirectional"))
      (node (ref "PROG") (pin "4") (pinfunction "4_4") (pintype "passive"))
    )
    (net (code "49") (name "Net-(PIC1-15_PGEC3{slash}RPB6{slash}PMD6{slash}RB6)") (class "Default")
      (node (ref "PIC1") (pin "15") (pinfunction "15_PGEC3/RPB6/PMD6/RB6_15") (pintype "bidirectional"))
      (node (ref "PROG") (pin "5") (pinfunction "5_5") (pintype "passive"))
      (node (ref "R27") (pin "2") (pinfunction "E_2") (pintype "passive"))
      (node (ref "SW1") (pin "G1") (pinfunction "G1_G1") (pintype "bidirectional"))
      (node (ref "SW10") (pin "G1") (pinfunction "G1_G1") (pintype "bidirectional"))
      (node (ref "SW11") (pin "G1") (pinfunction "G1_G1") (pintype "bidirectional"))
      (node (ref "SW12") (pin "G1") (pinfunction "G1_G1") (pintype "bidirectional"))
      (node (ref "SW2") (pin "G1") (pinfunction "G1_G1") (pintype "bidirectional"))
      (node (ref "SW3") (pin "G1") (pinfunction "G1_G1") (pintype "bidirectional"))
      (node (ref "SW4") (pin "G1") (pinfunction "G1_G1") (pintype "bidirectional"))
      (node (ref "SW5") (pin "G1") (pinfunction "G1_G1") (pintype "bidirectional"))
      (node (ref "SW6") (pin "G1") (pinfunction "G1_G1") (pintype "bidirectional"))
      (node (ref "SW7") (pin "G1") (pinfunction "G1_G1") (pintype "bidirectional"))
      (node (ref "SW8") (pin "G1") (pinfunction "G1_G1") (pintype "bidirectional"))
      (node (ref "SW9") (pin "G1") (pinfunction "G1_G1") (pintype "bidirectional"))
    )
    (net (code "50") (name "Net-(PIC1-16_TDI{slash}RPB7{slash}CTED3{slash}PMD5{slash}INT0{slash}RB7)") (class "Default")
      (node (ref "CN2") (pin "13") (pinfunction "13_13") (pintype "passive"))
      (node (ref "CN2") (pin "14") (pinfunction "14_14") (pintype "passive"))
      (node (ref "PIC1") (pin "16") (pinfunction "16_TDI/RPB7/CTED3/PMD5/INT0/RB7_16") (pintype "bidirectional"))
    )
    (net (code "51") (name "Net-(PIC1-20_VCAP)") (class "Default")
      (node (ref "C6") (pin "1") (pinfunction "1_1") (pintype "passive"))
      (node (ref "PIC1") (pin "20") (pinfunction "20_VCAP_20") (pintype "power_in"))
    )
    (net (code "52") (name "Net-(PIC1-21_PGED2{slash}RPB10{slash}CTED11{slash}PMD2{slash}RB10)") (class "Default")
      (node (ref "PIC1") (pin "21") (pinfunction "21_PGED2/RPB10/CTED11/PMD2/RB10_21") (pintype "bidirectional"))
      (node (ref "U$1") (pin "4") (pinfunction "04_~{LA}_4") (pintype "input"))
      (node (ref "U$2") (pin "4") (pinfunction "04_~{LA}_4") (pintype "input"))
      (node (ref "U$3") (pin "4") (pinfunction "04_~{LA}_4") (pintype "input"))
      (node (ref "U$4") (pin "4") (pinfunction "04_~{LA}_4") (pintype "input"))
      (node (ref "U$5") (pin "4") (pinfunction "04_~{LA}_4") (pintype "input"))
      (node (ref "U$6") (pin "4") (pinfunction "04_~{LA}_4") (pintype "input"))
      (node (ref "U$7") (pin "4") (pinfunction "04_~{LA}_4") (pintype "input"))
      (node (ref "U$8") (pin "4") (pinfunction "04_~{LA}_4") (pintype "input"))
    )
    (net (code "53") (name "Net-(PIC1-22_PGEC2{slash}TMS{slash}RPB11{slash}PMD1{slash}RB11)") (class "Default")
      (node (ref "PIC1") (pin "22") (pinfunction "22_PGEC2/TMS/RPB11/PMD1/RB11_22") (pintype "bidirectional"))
      (node (ref "U$7") (pin "2") (pinfunction "02_SDI_2") (pintype "input"))
    )
    (net (code "54") (name "Net-(PIC1-23_AN12{slash}PMD0{slash}RB12)") (class "Default")
      (node (ref "PIC1") (pin "23") (pinfunction "23_AN12/PMD0/RB12_23") (pintype "bidirectional"))
      (node (ref "U$1") (pin "13") (pinfunction "13_~{OE}_13") (pintype "input"))
      (node (ref "U$2") (pin "13") (pinfunction "13_~{OE}_13") (pintype "input"))
      (node (ref "U$3") (pin "13") (pinfunction "13_~{OE}_13") (pintype "input"))
      (node (ref "U$4") (pin "13") (pinfunction "13_~{OE}_13") (pintype "input"))
      (node (ref "U$5") (pin "13") (pinfunction "13_~{OE}_13") (pintype "input"))
      (node (ref "U$6") (pin "13") (pinfunction "13_~{OE}_13") (pintype "input"))
      (node (ref "U$7") (pin "13") (pinfunction "13_~{OE}_13") (pintype "input"))
      (node (ref "U$8") (pin "13") (pinfunction "13_~{OE}_13") (pintype "input"))
    )
    (net (code "55") (name "Net-(PIC1-24_AN11{slash}RPB13{slash}CTPLS{slash}PMRD{slash}RB13)") (class "Default")
      (node (ref "CN2") (pin "10") (pinfunction "10_10") (pintype "passive"))
      (node (ref "CN2") (pin "9") (pinfunction "9_9") (pintype "passive"))
      (node (ref "PIC1") (pin "24") (pinfunction "24_AN11/RPB13/CTPLS/PMRD/RB13_24") (pintype "bidirectional"))
    )
    (net (code "56") (name "Net-(PIC1-25_CVREFOUT{slash}AN10{slash}C3INB{slash}RPB14{slash}SCK1{slash}CTED5{slash}PMWR{slash}RB14)") (class "Default")
      (node (ref "CN2") (pin "7") (pinfunction "7_7") (pintype "passive"))
      (node (ref "CN2") (pin "8") (pinfunction "8_8") (pintype "passive"))
      (node (ref "PIC1") (pin "25") (pinfunction "25_CVREFOUT/AN10/C3INB/RPB14/SCK1/CTED5/PMWR/RB14_25") (pintype "bidirectional"))
      (node (ref "R14") (pin "1") (pinfunction "A_1") (pintype "passive"))
    )
    (net (code "57") (name "Net-(PIC1-26_AN9{slash}C3INA{slash}RPB15{slash}SCK2{slash}CTED6{slash}PMCS1{slash}RB15)") (class "Default")
      (node (ref "PIC1") (pin "26") (pinfunction "26_AN9/C3INA/RPB15/SCK2/CTED6/PMCS1/RB15_26") (pintype "bidirectional"))
      (node (ref "U$1") (pin "3") (pinfunction "03_CLK_3") (pintype "input"))
      (node (ref "U$2") (pin "3") (pinfunction "03_CLK_3") (pintype "input"))
      (node (ref "U$3") (pin "3") (pinfunction "03_CLK_3") (pintype "input"))
      (node (ref "U$4") (pin "3") (pinfunction "03_CLK_3") (pintype "input"))
      (node (ref "U$5") (pin "3") (pinfunction "03_CLK_3") (pintype "input"))
      (node (ref "U$6") (pin "3") (pinfunction "03_CLK_3") (pintype "input"))
      (node (ref "U$7") (pin "3") (pinfunction "03_CLK_3") (pintype "input"))
      (node (ref "U$8") (pin "3") (pinfunction "03_CLK_3") (pintype "input"))
    )
    (net (code "58") (name "Net-(Q2-B)") (class "Default")
      (node (ref "Q2") (pin "1") (pinfunction "B_1") (pintype "passive"))
      (node (ref "R17") (pin "2") (pinfunction "E_2") (pintype "passive"))
    )
    (net (code "59") (name "Net-(Q2-C)") (class "Default")
      (node (ref "Q2") (pin "3") (pinfunction "C_3") (pintype "passive"))
      (node (ref "R26") (pin "2") (pinfunction "E_2") (pintype "passive"))
    )
    (net (code "60") (name "Net-(R1-E)") (class "Default")
      (node (ref "R1") (pin "2") (pinfunction "E_2") (pintype "passive"))
      (node (ref "R11") (pin "2") (pinfunction "E_2") (pintype "passive"))
      (node (ref "R12") (pin "1") (pinfunction "A_1") (pintype "passive"))
      (node (ref "R15") (pin "2") (pinfunction "E_2") (pintype "passive"))
      (node (ref "R16") (pin "1") (pinfunction "A_1") (pintype "passive"))
      (node (ref "R2") (pin "1") (pinfunction "A_1") (pintype "passive"))
      (node (ref "R26") (pin "1") (pinfunction "A_1") (pintype "passive"))
      (node (ref "R3") (pin "2") (pinfunction "E_2") (pintype "passive"))
      (node (ref "R4") (pin "1") (pinfunction "A_1") (pintype "passive"))
      (node (ref "R5") (pin "2") (pinfunction "E_2") (pintype "passive"))
      (node (ref "R6") (pin "1") (pinfunction "A_1") (pintype "passive"))
      (node (ref "R7") (pin "2") (pinfunction "E_2") (pintype "passive"))
      (node (ref "R8") (pin "1") (pinfunction "A_1") (pintype "passive"))
    )
    (net (code "61") (name "Net-(R10-A)") (class "Default")
      (node (ref "R10") (pin "1") (pinfunction "A_1") (pintype "passive"))
      (node (ref "U$8") (pin "15") (pinfunction "15_REXT_15") (pintype "bidirectional"))
    )
    (net (code "62") (name "Net-(R10-E)") (class "Default")
      (node (ref "C20") (pin "P+") (pinfunction "P+_P+") (pintype "passive"))
      (node (ref "R10") (pin "2") (pinfunction "E_2") (pintype "passive"))
      (node (ref "R13") (pin "2") (pinfunction "E_2") (pintype "passive"))
      (node (ref "R18") (pin "2") (pinfunction "E_2") (pintype "passive"))
      (node (ref "R19") (pin "2") (pinfunction "E_2") (pintype "passive"))
      (node (ref "R20") (pin "2") (pinfunction "E_2") (pintype "passive"))
      (node (ref "R21") (pin "2") (pinfunction "E_2") (pintype "passive"))
      (node (ref "R22") (pin "2") (pinfunction "E_2") (pintype "passive"))
      (node (ref "R23") (pin "2") (pinfunction "E_2") (pintype "passive"))
      (node (ref "R31") (pin "2") (pinfunction "E_2") (pintype "passive"))
      (node (ref "R32") (pin "1") (pinfunction "A_1") (pintype "passive"))
    )
    (net (code "63") (name "Net-(R13-A)") (class "Default")
      (node (ref "R13") (pin "1") (pinfunction "A_1") (pintype "passive"))
      (node (ref "U$6") (pin "15") (pinfunction "15_REXT_15") (pintype "bidirectional"))
    )
    (net (code "64") (name "Net-(R18-A)") (class "Default")
      (node (ref "R18") (pin "1") (pinfunction "A_1") (pintype "passive"))
      (node (ref "U$7") (pin "15") (pinfunction "15_REXT_15") (pintype "bidirectional"))
    )
    (net (code "65") (name "Net-(R19-A)") (class "Default")
      (node (ref "R19") (pin "1") (pinfunction "A_1") (pintype "passive"))
      (node (ref "U$2") (pin "15") (pinfunction "15_REXT_15") (pintype "bidirectional"))
    )
    (net (code "66") (name "Net-(R20-A)") (class "Default")
      (node (ref "R20") (pin "1") (pinfunction "A_1") (pintype "passive"))
      (node (ref "U$1") (pin "15") (pinfunction "15_REXT_15") (pintype "bidirectional"))
    )
    (net (code "67") (name "Net-(R21-A)") (class "Default")
      (node (ref "R21") (pin "1") (pinfunction "A_1") (pintype "passive"))
      (node (ref "U$4") (pin "15") (pinfunction "15_REXT_15") (pintype "bidirectional"))
    )
    (net (code "68") (name "Net-(R22-A)") (class "Default")
      (node (ref "R22") (pin "1") (pinfunction "A_1") (pintype "passive"))
      (node (ref "U$5") (pin "15") (pinfunction "15_REXT_15") (pintype "bidirectional"))
    )
    (net (code "69") (name "Net-(R23-A)") (class "Default")
      (node (ref "R23") (pin "1") (pinfunction "A_1") (pintype "passive"))
      (node (ref "U$3") (pin "15") (pinfunction "15_REXT_15") (pintype "bidirectional"))
    )
    (net (code "70") (name "Net-(R51-A)") (class "Default")
      (node (ref "C28") (pin "2") (pinfunction "2_2") (pintype "passive"))
      (node (ref "R51") (pin "1") (pinfunction "A_1") (pintype "passive"))
    )
    (net (code "71") (name "Net-(R79-E)") (class "Default")
      (node (ref "R79") (pin "2") (pinfunction "E_2") (pintype "passive"))
      (node (ref "SJ2") (pin "2") (pinfunction "2_2") (pintype "passive"))
      (node (ref "U$1") (pin "14") (pinfunction "14_SDO_14") (pintype "output"))
    )
    (net (code "72") (name "Net-(SJ1-1)") (class "Default")
      (node (ref "SJ1") (pin "3") (pinfunction "1_3") (pintype "passive"))
      (node (ref "SJ5") (pin "2") (pinfunction "2_2") (pintype "passive"))
      (node (ref "U$2") (pin "2") (pinfunction "02_SDI_2") (pintype "input"))
      (node (ref "U$6") (pin "14") (pinfunction "14_SDO_14") (pintype "output"))
    )
    (net (code "73") (name "Net-(SJ2-1)") (class "Default")
      (node (ref "SJ2") (pin "3") (pinfunction "1_3") (pintype "passive"))
      (node (ref "SJ6") (pin "2") (pinfunction "2_2") (pintype "passive"))
      (node (ref "U$1") (pin "2") (pinfunction "02_SDI_2") (pintype "input"))
      (node (ref "U$3") (pin "14") (pinfunction "14_SDO_14") (pintype "output"))
    )
    (net (code "74") (name "Net-(SJ3-1)") (class "Default")
      (node (ref "SJ3") (pin "3") (pinfunction "1_3") (pintype "passive"))
      (node (ref "U$4") (pin "2") (pinfunction "02_SDI_2") (pintype "input"))
      (node (ref "U$8") (pin "14") (pinfunction "14_SDO_14") (pintype "output"))
    )
    (net (code "75") (name "Net-(SJ4-1)") (class "Default")
      (node (ref "SJ3") (pin "2") (pinfunction "2_2") (pintype "passive"))
      (node (ref "SJ4") (pin "3") (pinfunction "1_3") (pintype "passive"))
      (node (ref "U$4") (pin "14") (pinfunction "14_SDO_14") (pintype "output"))
      (node (ref "U$5") (pin "2") (pinfunction "02_SDI_2") (pintype "input"))
    )
    (net (code "76") (name "Net-(SJ5-1)") (class "Default")
      (node (ref "SJ4") (pin "2") (pinfunction "2_2") (pintype "passive"))
      (node (ref "SJ5") (pin "3") (pinfunction "1_3") (pintype "passive"))
      (node (ref "U$5") (pin "14") (pinfunction "14_SDO_14") (pintype "output"))
      (node (ref "U$6") (pin "2") (pinfunction "02_SDI_2") (pintype "input"))
    )
    (net (code "77") (name "Net-(SJ6-1)") (class "Default")
      (node (ref "SJ1") (pin "2") (pinfunction "2_2") (pintype "passive"))
      (node (ref "SJ6") (pin "3") (pinfunction "1_3") (pintype "passive"))
      (node (ref "U$2") (pin "14") (pinfunction "14_SDO_14") (pintype "output"))
      (node (ref "U$3") (pin "2") (pinfunction "02_SDI_2") (pintype "input"))
    )
    (net (code "78") (name "Net-(SW1B-P)") (class "Default")
      (node (ref "SW1") (pin "P-") (pinfunction "P_P-") (pintype "bidirectional"))
      (node (ref "U$2") (pin "7") (pinfunction "07_OUT2_7") (pintype "output"))
    )
    (net (code "79") (name "Net-(SW1B-Z)") (class "Default")
      (node (ref "SW1") (pin "Z-") (pinfunction "Z_Z-") (pintype "bidirectional"))
      (node (ref "U$2") (pin "6") (pinfunction "06_OUT1_6") (pintype "output"))
    )
    (net (code "80") (name "Net-(SW2B-P)") (class "Default")
      (node (ref "SW2") (pin "P-") (pinfunction "P_P-") (pintype "bidirectional"))
      (node (ref "U$2") (pin "11") (pinfunction "11_OUT6_11") (pintype "output"))
    )
    (net (code "81") (name "Net-(SW2B-Z)") (class "Default")
      (node (ref "SW2") (pin "Z-") (pinfunction "Z_Z-") (pintype "bidirectional"))
      (node (ref "U$2") (pin "10") (pinfunction "10_OUT5_10") (pintype "output"))
    )
    (net (code "82") (name "Net-(SW3B-P)") (class "Default")
      (node (ref "SW3") (pin "P-") (pinfunction "P_P-") (pintype "bidirectional"))
      (node (ref "U$1") (pin "7") (pinfunction "07_OUT2_7") (pintype "output"))
    )
    (net (code "83") (name "Net-(SW3B-Z)") (class "Default")
      (node (ref "SW3") (pin "Z-") (pinfunction "Z_Z-") (pintype "bidirectional"))
      (node (ref "U$1") (pin "6") (pinfunction "06_OUT1_6") (pintype "output"))
    )
    (net (code "84") (name "Net-(SW4B-P)") (class "Default")
      (node (ref "SW4") (pin "P-") (pinfunction "P_P-") (pintype "bidirectional"))
      (node (ref "U$1") (pin "11") (pinfunction "11_OUT6_11") (pintype "output"))
    )
    (net (code "85") (name "Net-(SW4B-Z)") (class "Default")
      (node (ref "SW4") (pin "Z-") (pinfunction "Z_Z-") (pintype "bidirectional"))
      (node (ref "U$1") (pin "10") (pinfunction "10_OUT5_10") (pintype "output"))
    )
    (net (code "86") (name "Net-(SW5B-P)") (class "Default")
      (node (ref "SW5") (pin "P-") (pinfunction "P_P-") (pintype "bidirectional"))
      (node (ref "U$4") (pin "7") (pinfunction "07_OUT2_7") (pintype "output"))
    )
    (net (code "87") (name "Net-(SW5B-Z)") (class "Default")
      (node (ref "SW5") (pin "Z-") (pinfunction "Z_Z-") (pintype "bidirectional"))
      (node (ref "U$4") (pin "6") (pinfunction "06_OUT1_6") (pintype "output"))
    )
    (net (code "88") (name "Net-(SW6B-P)") (class "Default")
      (node (ref "SW6") (pin "P-") (pinfunction "P_P-") (pintype "bidirectional"))
      (node (ref "U$4") (pin "11") (pinfunction "11_OUT6_11") (pintype "output"))
    )
    (net (code "89") (name "Net-(SW6B-Z)") (class "Default")
      (node (ref "SW6") (pin "Z-") (pinfunction "Z_Z-") (pintype "bidirectional"))
      (node (ref "U$4") (pin "10") (pinfunction "10_OUT5_10") (pintype "output"))
    )
    (net (code "90") (name "Net-(SW7B-P)") (class "Default")
      (node (ref "SW7") (pin "P-") (pinfunction "P_P-") (pintype "bidirectional"))
      (node (ref "U$5") (pin "7") (pinfunction "07_OUT2_7") (pintype "output"))
    )
    (net (code "91") (name "Net-(SW7B-Z)") (class "Default")
      (node (ref "SW7") (pin "Z-") (pinfunction "Z_Z-") (pintype "bidirectional"))
      (node (ref "U$5") (pin "6") (pinfunction "06_OUT1_6") (pintype "output"))
    )
    (net (code "92") (name "Net-(SW8B-P)") (class "Default")
      (node (ref "SW8") (pin "P-") (pinfunction "P_P-") (pintype "bidirectional"))
      (node (ref "U$5") (pin "11") (pinfunction "11_OUT6_11") (pintype "output"))
    )
    (net (code "93") (name "Net-(SW8B-Z)") (class "Default")
      (node (ref "SW8") (pin "Z-") (pinfunction "Z_Z-") (pintype "bidirectional"))
      (node (ref "U$5") (pin "10") (pinfunction "10_OUT5_10") (pintype "output"))
    )
    (net (code "94") (name "Net-(SW9B-P)") (class "Default")
      (node (ref "SW9") (pin "P-") (pinfunction "P_P-") (pintype "bidirectional"))
      (node (ref "U$6") (pin "7") (pinfunction "07_OUT2_7") (pintype "output"))
    )
    (net (code "95") (name "Net-(SW9B-Z)") (class "Default")
      (node (ref "SW9") (pin "Z-") (pinfunction "Z_Z-") (pintype "bidirectional"))
      (node (ref "U$6") (pin "6") (pinfunction "06_OUT1_6") (pintype "output"))
    )
    (net (code "96") (name "Net-(SW10B-P)") (class "Default")
      (node (ref "SW10") (pin "P-") (pinfunction "P_P-") (pintype "bidirectional"))
      (node (ref "U$6") (pin "11") (pinfunction "11_OUT6_11") (pintype "output"))
    )
    (net (code "97") (name "Net-(SW10B-Z)") (class "Default")
      (node (ref "SW10") (pin "Z-") (pinfunction "Z_Z-") (pintype "bidirectional"))
      (node (ref "U$6") (pin "10") (pinfunction "10_OUT5_10") (pintype "output"))
    )
    (net (code "98") (name "Net-(SW11B-P)") (class "Default")
      (node (ref "SW11") (pin "P-") (pinfunction "P_P-") (pintype "bidirectional"))
      (node (ref "U$3") (pin "7") (pinfunction "07_OUT2_7") (pintype "output"))
    )
    (net (code "99") (name "Net-(SW11B-Z)") (class "Default")
      (node (ref "SW11") (pin "Z-") (pinfunction "Z_Z-") (pintype "bidirectional"))
      (node (ref "U$3") (pin "6") (pinfunction "06_OUT1_6") (pintype "output"))
    )
    (net (code "100") (name "Net-(SW12B-P)") (class "Default")
      (node (ref "SW12") (pin "P-") (pinfunction "P_P-") (pintype "bidirectional"))
      (node (ref "U$3") (pin "11") (pinfunction "11_OUT6_11") (pintype "output"))
    )
    (net (code "101") (name "Net-(SW12B-Z)") (class "Default")
      (node (ref "SW12") (pin "Z-") (pinfunction "Z_Z-") (pintype "bidirectional"))
      (node (ref "U$3") (pin "10") (pinfunction "10_OUT5_10") (pintype "output"))
    )
    (net (code "102") (name "Net-(U$1-08_OUT3)") (class "Default")
      (node (ref "SW3") (pin "G2") (pinfunction "G2_G2") (pintype "bidirectional"))
      (node (ref "U$1") (pin "8") (pinfunction "08_OUT3_8") (pintype "output"))
    )
    (net (code "103") (name "Net-(U$1-12_OUT7)") (class "Default")
      (node (ref "SW4") (pin "G2") (pinfunction "G2_G2") (pintype "bidirectional"))
      (node (ref "U$1") (pin "12") (pinfunction "12_OUT7_12") (pintype "output"))
    )
    (net (code "104") (name "Net-(U$2-08_OUT3)") (class "Default")
      (node (ref "SW1") (pin "G2") (pinfunction "G2_G2") (pintype "bidirectional"))
      (node (ref "U$2") (pin "8") (pinfunction "08_OUT3_8") (pintype "output"))
    )
    (net (code "105") (name "Net-(U$2-12_OUT7)") (class "Default")
      (node (ref "SW2") (pin "G2") (pinfunction "G2_G2") (pintype "bidirectional"))
      (node (ref "U$2") (pin "12") (pinfunction "12_OUT7_12") (pintype "output"))
    )
    (net (code "106") (name "Net-(U$3-08_OUT3)") (class "Default")
      (node (ref "SW11") (pin "G2") (pinfunction "G2_G2") (pintype "bidirectional"))
      (node (ref "U$3") (pin "8") (pinfunction "08_OUT3_8") (pintype "output"))
    )
    (net (code "107") (name "Net-(U$3-12_OUT7)") (class "Default")
      (node (ref "SW12") (pin "G2") (pinfunction "G2_G2") (pintype "bidirectional"))
      (node (ref "U$3") (pin "12") (pinfunction "12_OUT7_12") (pintype "output"))
    )
    (net (code "108") (name "Net-(U$4-08_OUT3)") (class "Default")
      (node (ref "SW5") (pin "G2") (pinfunction "G2_G2") (pintype "bidirectional"))
      (node (ref "U$4") (pin "8") (pinfunction "08_OUT3_8") (pintype "output"))
    )
    (net (code "109") (name "Net-(U$4-12_OUT7)") (class "Default")
      (node (ref "SW6") (pin "G2") (pinfunction "G2_G2") (pintype "bidirectional"))
      (node (ref "U$4") (pin "12") (pinfunction "12_OUT7_12") (pintype "output"))
    )
    (net (code "110") (name "Net-(U$5-08_OUT3)") (class "Default")
      (node (ref "SW7") (pin "G2") (pinfunction "G2_G2") (pintype "bidirectional"))
      (node (ref "U$5") (pin "8") (pinfunction "08_OUT3_8") (pintype "output"))
    )
    (net (code "111") (name "Net-(U$5-12_OUT7)") (class "Default")
      (node (ref "SW8") (pin "G2") (pinfunction "G2_G2") (pintype "bidirectional"))
      (node (ref "U$5") (pin "12") (pinfunction "12_OUT7_12") (pintype "output"))
    )
    (net (code "112") (name "Net-(U$6-08_OUT3)") (class "Default")
      (node (ref "SW9") (pin "G2") (pinfunction "G2_G2") (pintype "bidirectional"))
      (node (ref "U$6") (pin "8") (pinfunction "08_OUT3_8") (pintype "output"))
    )
    (net (code "113") (name "Net-(U$6-12_OUT7)") (class "Default")
      (node (ref "SW10") (pin "G2") (pinfunction "G2_G2") (pintype "bidirectional"))
      (node (ref "U$6") (pin "12") (pinfunction "12_OUT7_12") (pintype "output"))
    )
    (net (code "114") (name "Net-(U$7-14_SDO)") (class "Default")
      (node (ref "U$7") (pin "14") (pinfunction "14_SDO_14") (pintype "output"))
      (node (ref "U$8") (pin "2") (pinfunction "02_SDI_2") (pintype "input"))
    )
    (net (code "115") (name "unconnected-(PIC1-02_VREF+{slash}VREF+{slash}AN0{slash}C3INC{slash}RPA0{slash}CTED1{slash}RA0-Pad2)") (class "Default")
      (node (ref "PIC1") (pin "2") (pinfunction "02_VREF+/VREF+/AN0/C3INC/RPA0/CTED1/RA0_2") (pintype "bidirectional"))
    )
    (net (code "116") (name "unconnected-(PIC1-03_VREF-{slash}CVREF-{slash}AN1{slash}RPA1{slash}CTED2{slash}RA1-Pad3)") (class "Default")
      (node (ref "PIC1") (pin "3") (pinfunction "03_VREF-/CVREF-/AN1/RPA1/CTED2/RA1_3") (pintype "bidirectional"))
    )
    (net (code "117") (name "unconnected-(PIC1-04_PGED1{slash}AN2{slash}C1IND{slash}C2INB{slash}C3IND{slash}RPB0{slash}RB0-Pad4)") (class "Default")
      (node (ref "PIC1") (pin "4") (pinfunction "04_PGED1/AN2/C1IND/C2INB/C3IND/RPB0/RB0_4") (pintype "bidirectional"))
    )
    (net (code "118") (name "unconnected-(PIC1-05_PGEC1{slash}AN3{slash}C1INC{slash}C2INA{slash}RPB1{slash}CTED12{slash}RB1-Pad5)") (class "Default")
      (node (ref "PIC1") (pin "5") (pinfunction "05_PGEC1/AN3/C1INC/C2INA/RPB1/CTED12/RB1_5") (pintype "bidirectional"))
    )
    (net (code "119") (name "unconnected-(PIC1-07_AN5{slash}C1INA{slash}C2INC{slash}RTCC{slash}RPB3{slash}SCL2{slash}RB3-Pad7)") (class "Default")
      (node (ref "PIC1") (pin "7") (pinfunction "07_AN5/C1INA/C2INC/RTCC/RPB3/SCL2/RB3_7") (pintype "bidirectional"))
    )
    (net (code "120") (name "unconnected-(PIC1-11_SOSCI{slash}RPB4{slash}RB4-Pad11)") (class "Default")
      (node (ref "PIC1") (pin "11") (pinfunction "11_SOSCI/RPB4/RB4_11") (pintype "bidirectional"))
    )
    (net (code "121") (name "unconnected-(PIC1-17_TCK{slash}RPB8{slash}SCL1{slash}CTED10{slash}PMD4{slash}RB8-Pad17)") (class "Default")
      (node (ref "PIC1") (pin "17") (pinfunction "17_TCK/RPB8/SCL1/CTED10/PMD4/RB8_17") (pintype "bidirectional"))
    )
    (net (code "122") (name "unconnected-(PIC1-18_TDO{slash}RPB9{slash}SDA1{slash}CTED4{slash}PMD3{slash}RB9-Pad18)") (class "Default")
      (node (ref "PIC1") (pin "18") (pinfunction "18_TDO/RPB9/SDA1/CTED4/PMD3/RB9_18") (pintype "bidirectional"))
    )
    (net (code "123") (name "unconnected-(U$7-11_OUT6-Pad11)") (class "Default")
      (node (ref "U$7") (pin "11") (pinfunction "11_OUT6_11") (pintype "output"))
    )
    (net (code "124") (name "unconnected-(U$7-12_OUT7-Pad12)") (class "Default")
      (node (ref "U$7") (pin "12") (pinfunction "12_OUT7_12") (pintype "output"))
    )
    (net (code "125") (name "unconnected-(U$8-11_OUT6-Pad11)") (class "Default")
      (node (ref "U$8") (pin "11") (pinfunction "11_OUT6_11") (pintype "output"))
    )
    (net (code "126") (name "unconnected-(U$8-12_OUT7-Pad12)") (class "Default")
      (node (ref "U$8") (pin "12") (pinfunction "12_OUT7_12") (pintype "output"))
    )
  )
)
